# ProProject_AstrOnStep_2024-04-22.net
KiCad netlist of a schematic drawn in EasyEDA Pro
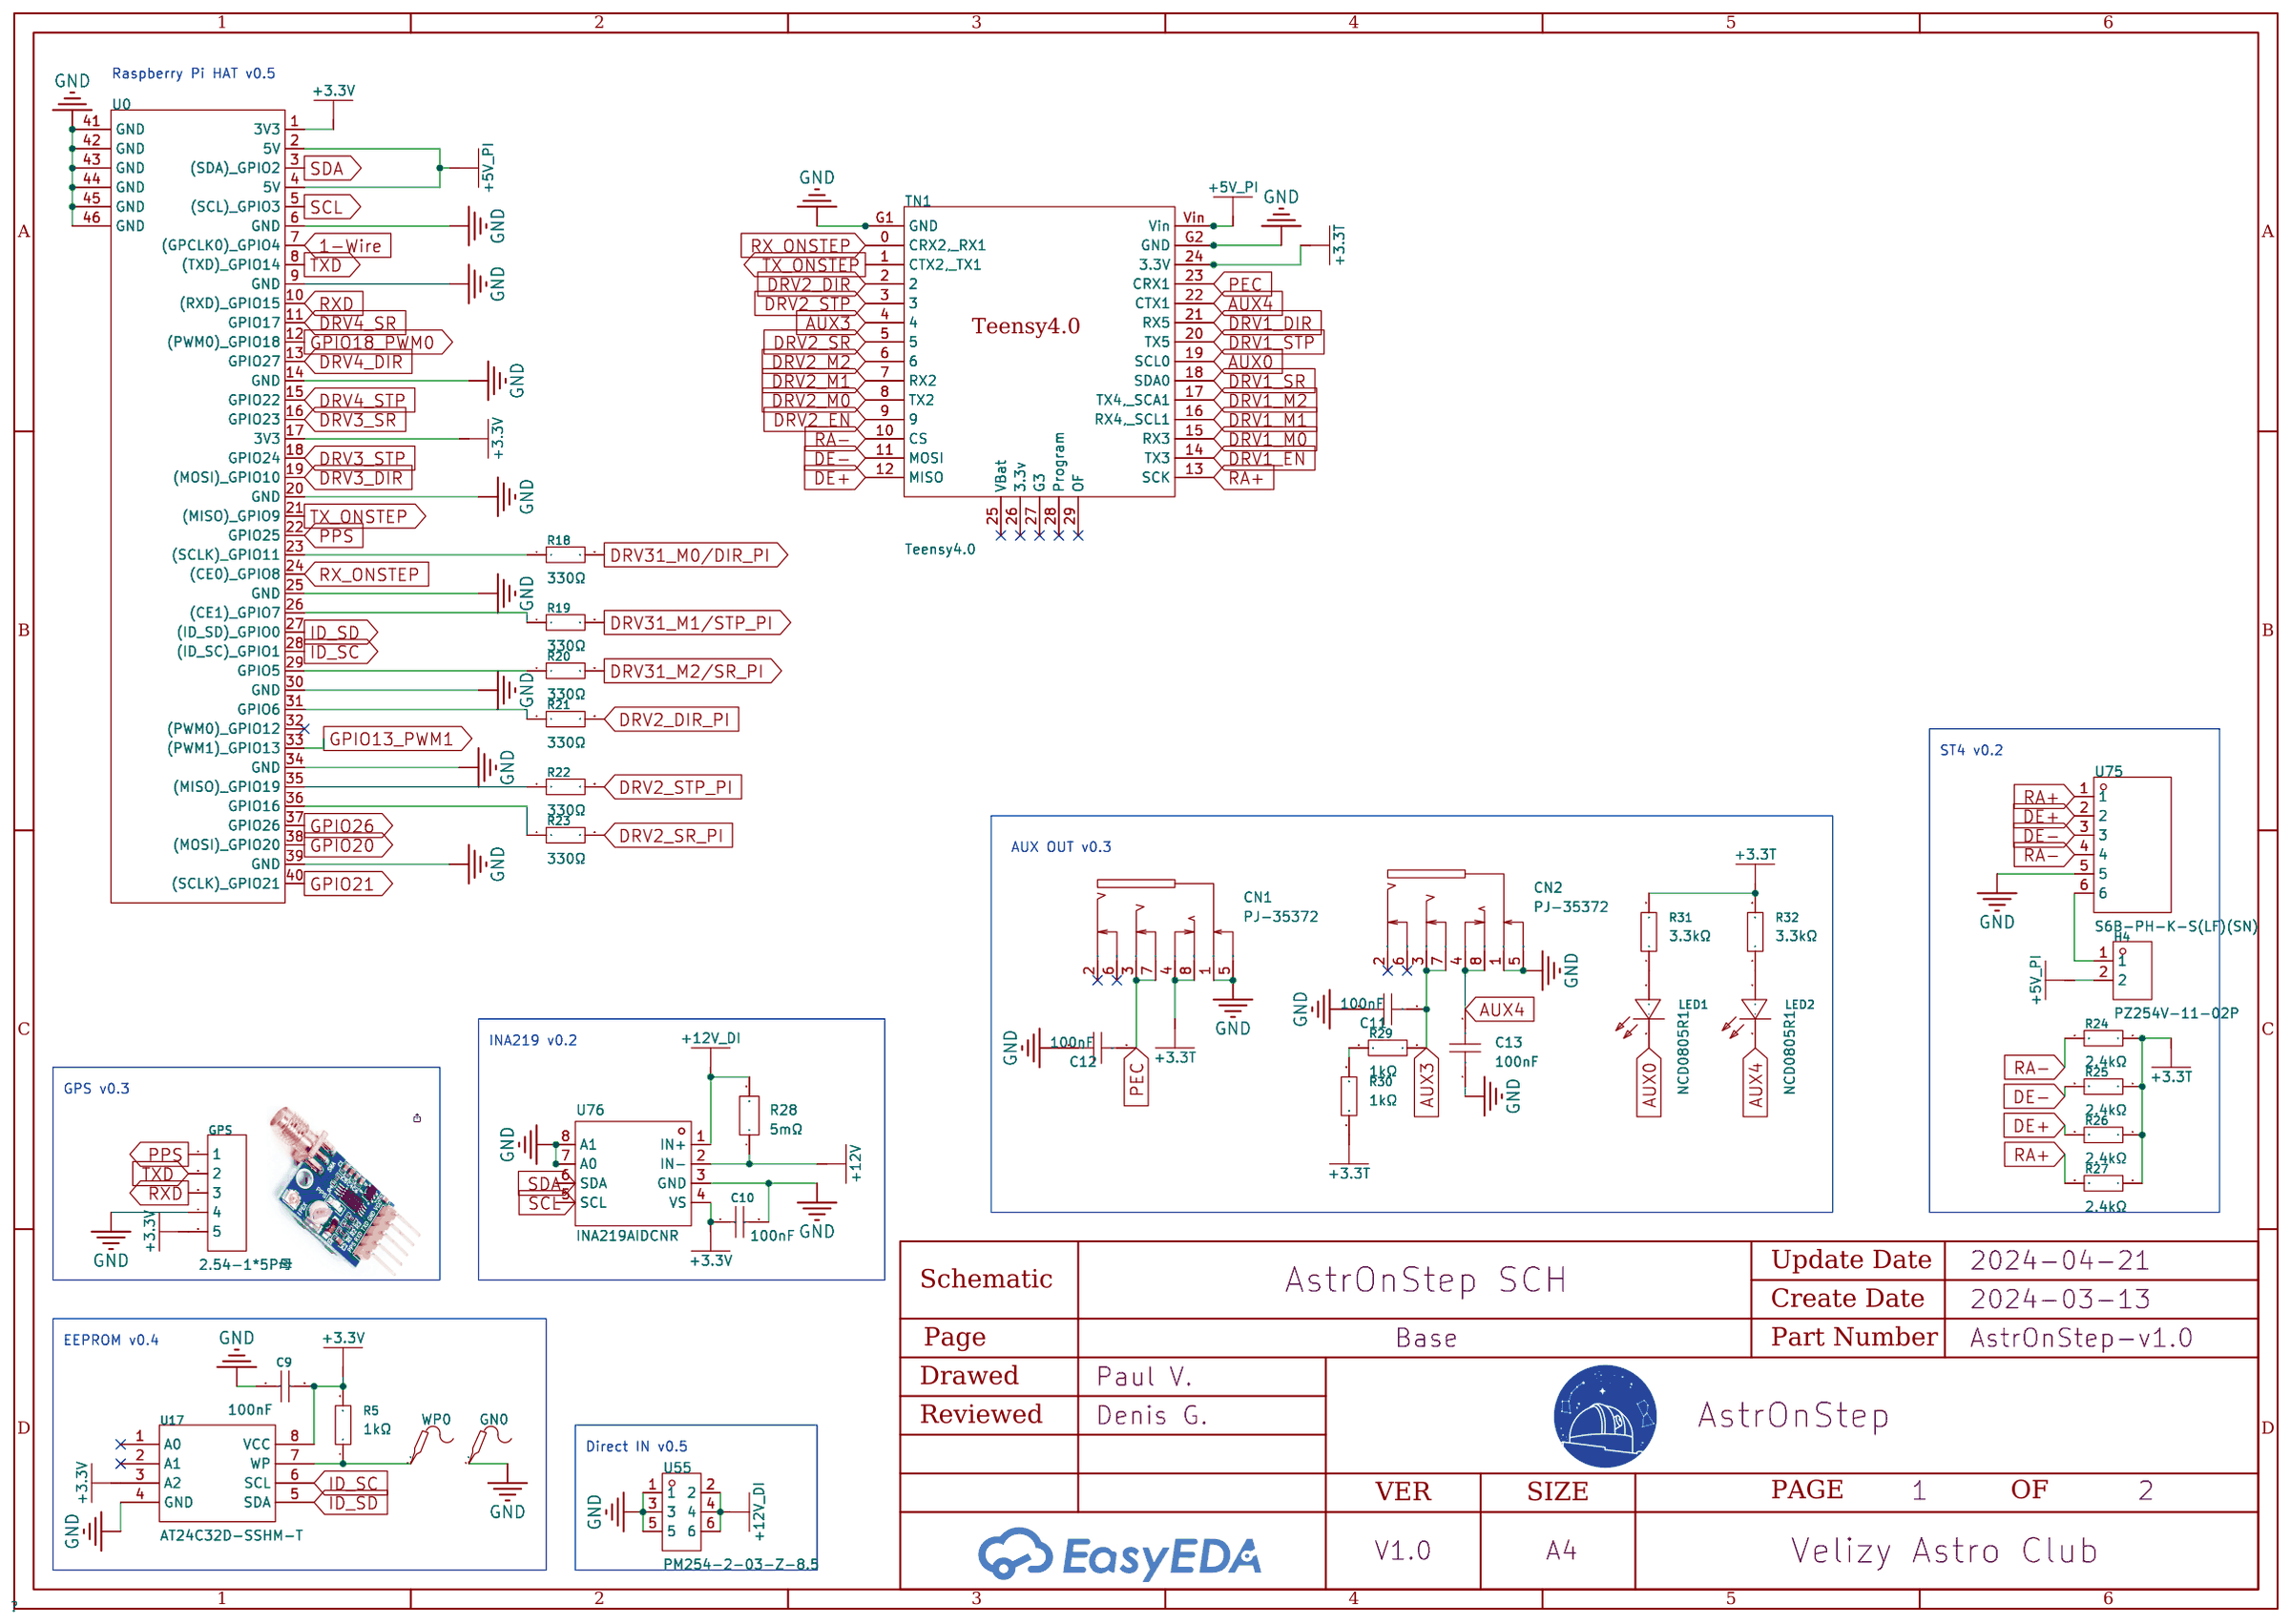
[diagram p0: Base]
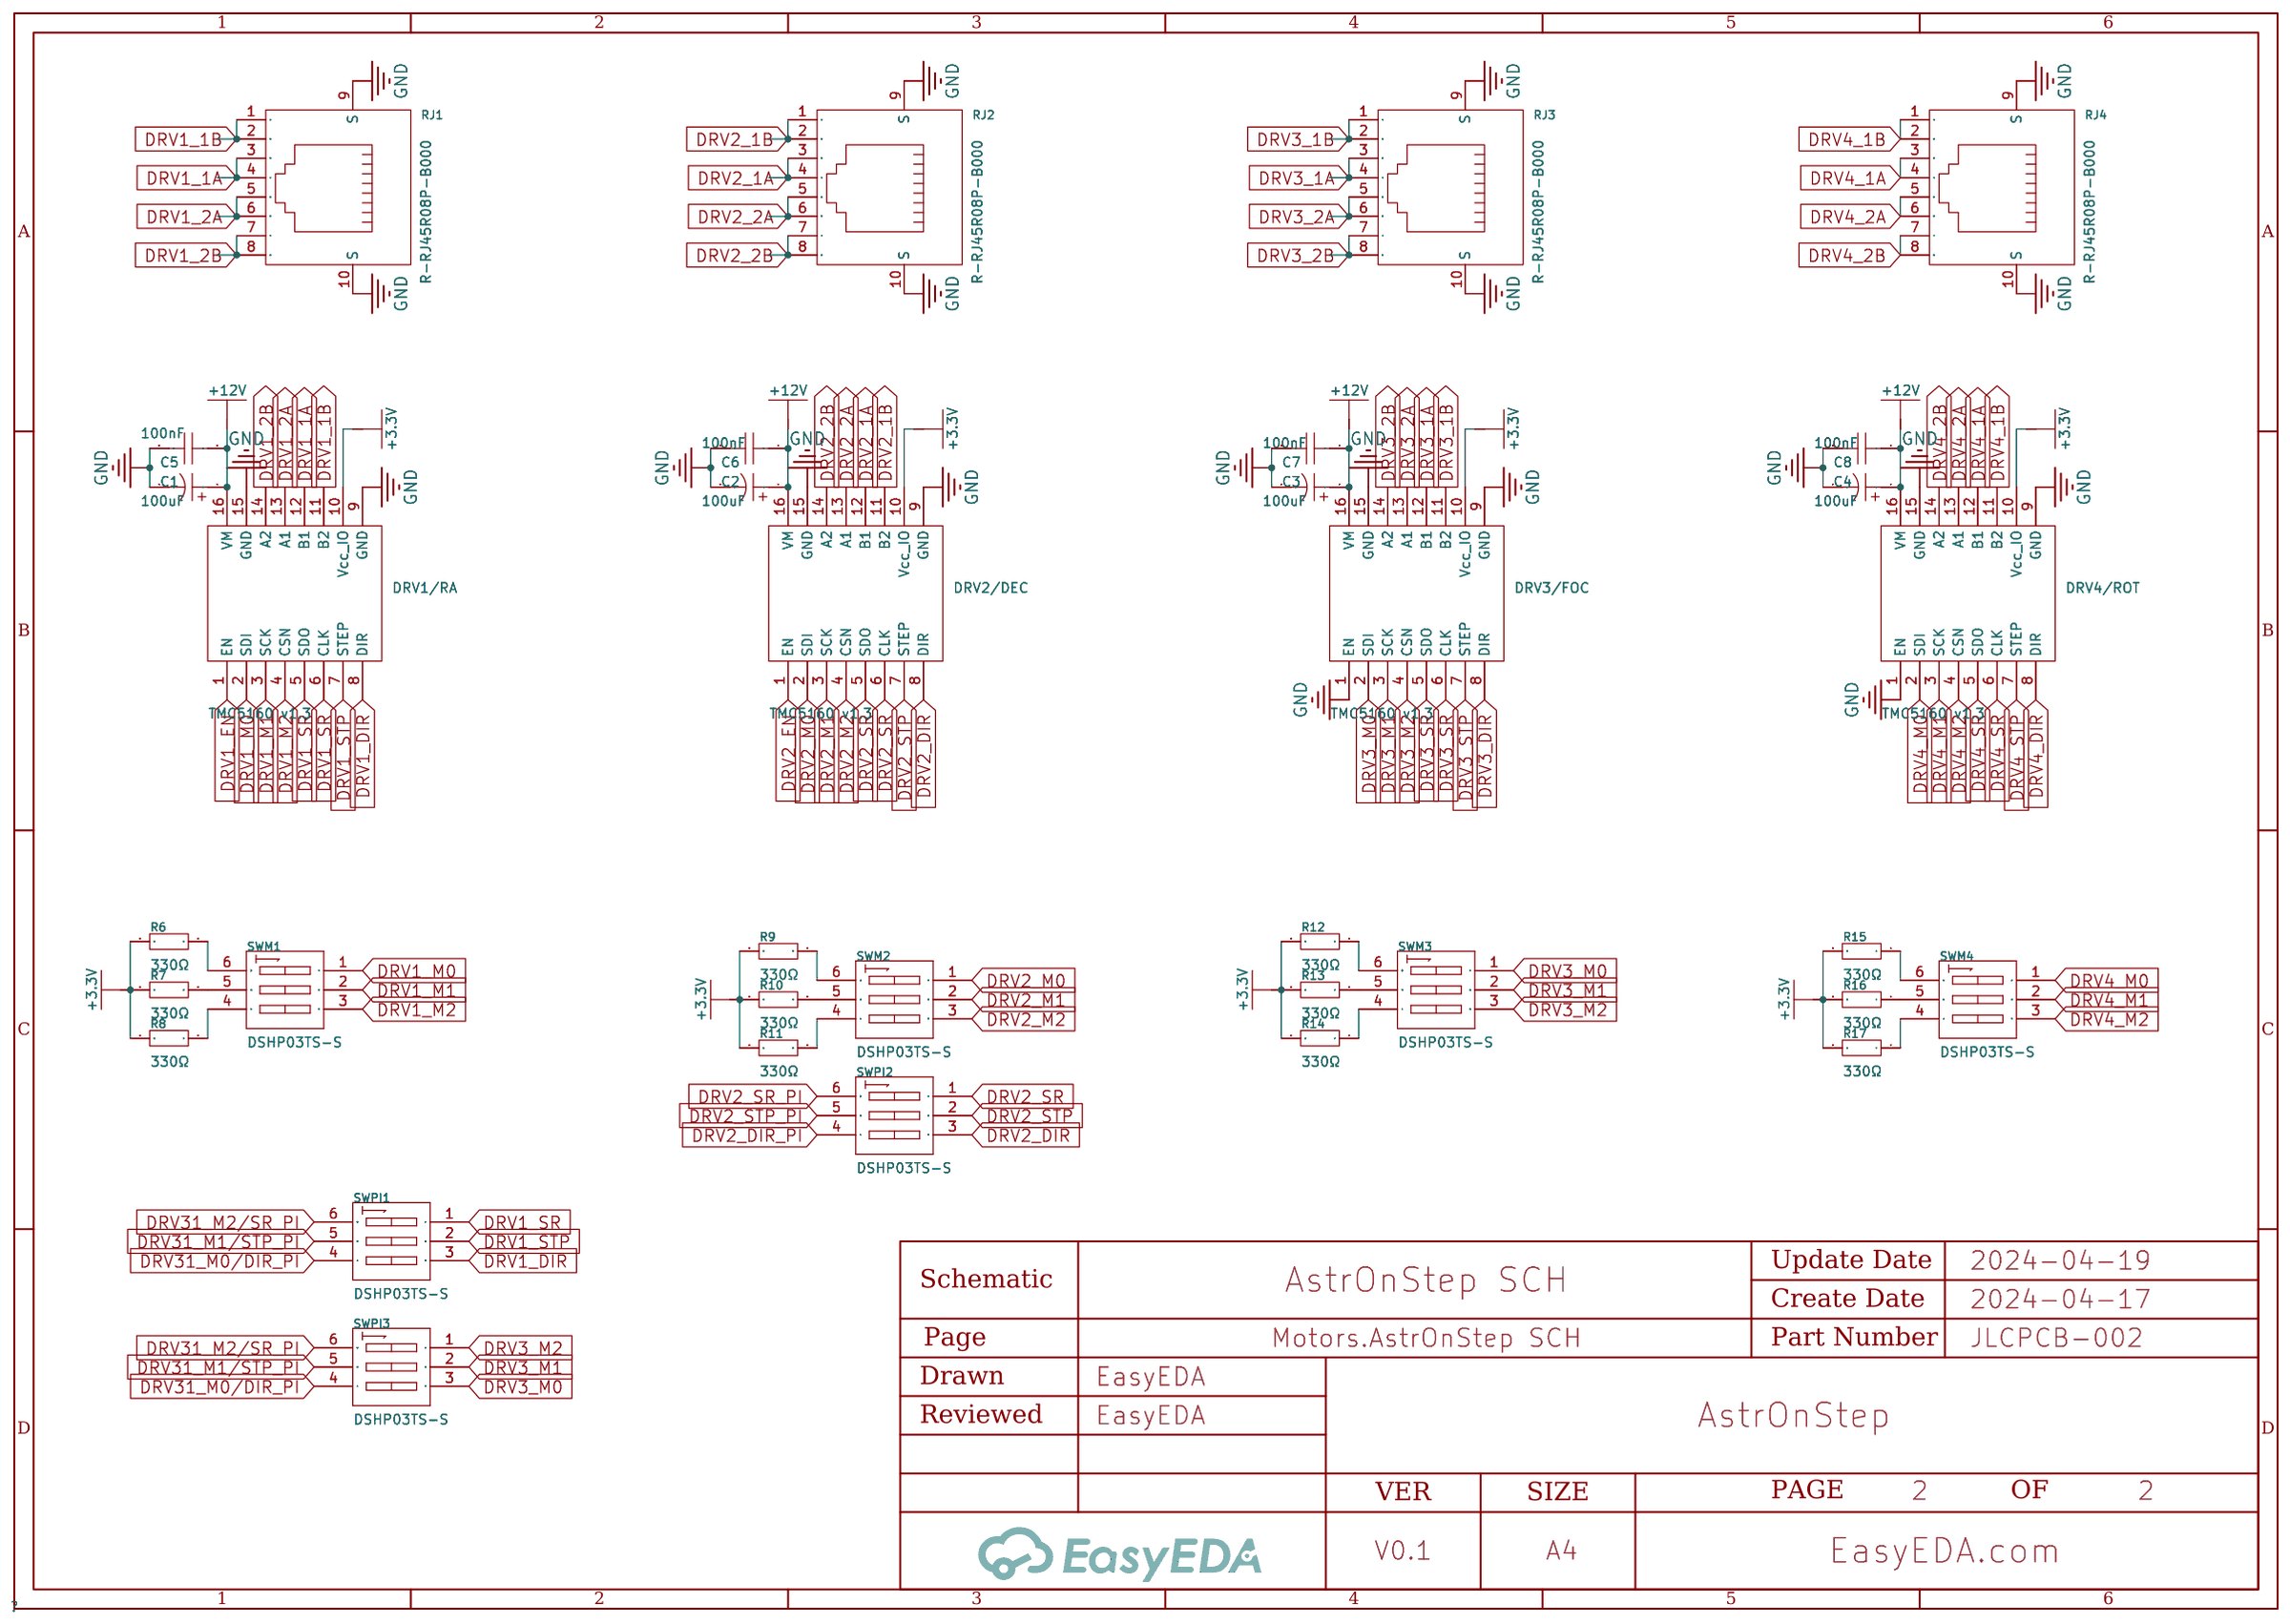
[diagram p1: Motors]

(export (version "E")
  (design (tool "Eeschema 10.0.6"))
  (components
    (comp (ref "C9")
      (value "100nF")
      (footprint "easyedapro:C0402")
      (fields
        (field (name "Manufacturer Part") "CL05B104KO5NNNC")
        (field (name "Manufacturer") "SAMSUNG(三星)")
      )
      (libsource (lib "easyedapro") (part "CL05B104KO5NNNC"))
    )
    (comp (ref "C10")
      (value "100nF")
      (footprint "easyedapro:C0402")
      (fields
        (field (name "Manufacturer Part") "CL05B104KO5NNNC")
        (field (name "Manufacturer") "SAMSUNG(三星)")
      )
      (libsource (lib "easyedapro") (part "CL05B104KO5NNNC"))
    )
    (comp (ref "C11")
      (value "100nF")
      (footprint "easyedapro:C0603")
      (fields
        (field (name "Manufacturer Part") "CC0603KRX7R9BB104")
        (field (name "Manufacturer") "YAGEO(国巨)")
      )
      (libsource (lib "easyedapro") (part "CC0603KRX7R9BB104"))
    )
    (comp (ref "C12")
      (value "100nF")
      (footprint "easyedapro:C0603")
      (fields
        (field (name "Manufacturer Part") "CC0603KRX7R9BB104")
        (field (name "Manufacturer") "YAGEO(国巨)")
      )
      (libsource (lib "easyedapro") (part "CC0603KRX7R9BB104"))
    )
    (comp (ref "C13")
      (value "100nF")
      (footprint "easyedapro:C0603")
      (fields
        (field (name "Manufacturer Part") "CC0603KRX7R9BB104")
        (field (name "Manufacturer") "YAGEO(国巨)")
      )
      (libsource (lib "easyedapro") (part "CC0603KRX7R9BB104"))
    )
    (comp (ref "CN1")
      (value "PJ-35372")
      (footprint "easyedapro:AUDIO-TH_PJ-35372")
      (fields (field (name "Manufacturer") "XKB Connectivity(中国星坤)"))
      (libsource (lib "easyedapro") (part "PJ-35372"))
    )
    (comp (ref "CN2")
      (value "PJ-35372")
      (footprint "easyedapro:AUDIO-TH_PJ-35372")
      (fields (field (name "Manufacturer") "XKB Connectivity(中国星坤)"))
      (libsource (lib "easyedapro") (part "PJ-35372"))
    )
    (comp (ref "GN0")
      (value "~")
      (footprint "easyedapro:Test-Point-0.5mm")
      (description "Test Point 测试点")
      (libsource (lib "easyedapro") (part "Test-Point"))
    )
    (comp (ref "GPS")
      (value "2.54-1*5P母")
      (footprint "easyedapro:HDR-TH_5P-P2.54-V-F")
      (fields (field (name "Manufacturer") "BOOMELE(博穆精密)"))
      (libsource (lib "easyedapro") (part "Header-Female-2.54_1x5"))
    )
    (comp (ref "H4")
      (value "PZ254V-11-02P")
      (footprint "easyedapro:HDR-TH_2P-P2.54-V-M")
      (fields (field (name "Manufacturer") "XFCN(兴飞)"))
      (libsource (lib "easyedapro") (part "PZ254V-11-02P"))
    )
    (comp (ref "LED1")
      (value "NCD0805R1")
      (footprint "easyedapro:LED0805-R-RD")
      (fields (field (name "Manufacturer") "国星光电"))
      (libsource (lib "easyedapro") (part "FC-2012HRK-620D"))
    )
    (comp (ref "LED2")
      (value "NCD0805R1")
      (footprint "easyedapro:LED0805-R-RD")
      (fields (field (name "Manufacturer") "国星光电"))
      (libsource (lib "easyedapro") (part "FC-2012HRK-620D"))
    )
    (comp (ref "R5")
      (value "1kΩ")
      (footprint "easyedapro:R0402")
      (fields
        (field (name "Manufacturer Part") "0402WGF1001TCE")
        (field (name "Manufacturer") "UNI-ROYAL(厚声)")
      )
      (libsource (lib "easyedapro") (part "0402WGF1001TCE"))
    )
    (comp (ref "R18")
      (value "330Ω")
      (footprint "easyedapro:R0402")
      (fields
        (field (name "Manufacturer Part") "0402WGF3300TCE")
        (field (name "Manufacturer") "UNI-ROYAL(厚声)")
      )
      (libsource (lib "easyedapro") (part "0402WGF3300TCE"))
    )
    (comp (ref "R19")
      (value "330Ω")
      (footprint "easyedapro:R0402")
      (fields
        (field (name "Manufacturer Part") "0402WGF3300TCE")
        (field (name "Manufacturer") "UNI-ROYAL(厚声)")
      )
      (libsource (lib "easyedapro") (part "0402WGF3300TCE"))
    )
    (comp (ref "R20")
      (value "330Ω")
      (footprint "easyedapro:R0402")
      (fields
        (field (name "Manufacturer Part") "0402WGF3300TCE")
        (field (name "Manufacturer") "UNI-ROYAL(厚声)")
      )
      (libsource (lib "easyedapro") (part "0402WGF3300TCE"))
    )
    (comp (ref "R21")
      (value "330Ω")
      (footprint "easyedapro:R0402")
      (fields
        (field (name "Manufacturer Part") "0402WGF3300TCE")
        (field (name "Manufacturer") "UNI-ROYAL(厚声)")
      )
      (libsource (lib "easyedapro") (part "0402WGF3300TCE"))
    )
    (comp (ref "R22")
      (value "330Ω")
      (footprint "easyedapro:R0402")
      (fields
        (field (name "Manufacturer Part") "0402WGF3300TCE")
        (field (name "Manufacturer") "UNI-ROYAL(厚声)")
      )
      (libsource (lib "easyedapro") (part "0402WGF3300TCE"))
    )
    (comp (ref "R23")
      (value "330Ω")
      (footprint "easyedapro:R0402")
      (fields
        (field (name "Manufacturer Part") "0402WGF3300TCE")
        (field (name "Manufacturer") "UNI-ROYAL(厚声)")
      )
      (libsource (lib "easyedapro") (part "0402WGF3300TCE"))
    )
    (comp (ref "R24")
      (value "2.4kΩ")
      (footprint "easyedapro:R0603")
      (fields
        (field (name "Manufacturer Part") "0603WAF2401T5E")
        (field (name "Manufacturer") "UNI-ROYAL(厚声)")
      )
      (libsource (lib "easyedapro") (part "0603WAF2401T5E"))
    )
    (comp (ref "R25")
      (value "2.4kΩ")
      (footprint "easyedapro:R0603")
      (fields
        (field (name "Manufacturer Part") "0603WAF2401T5E")
        (field (name "Manufacturer") "UNI-ROYAL(厚声)")
      )
      (libsource (lib "easyedapro") (part "0603WAF2401T5E"))
    )
    (comp (ref "R26")
      (value "2.4kΩ")
      (footprint "easyedapro:R0603")
      (fields
        (field (name "Manufacturer Part") "0603WAF2401T5E")
        (field (name "Manufacturer") "UNI-ROYAL(厚声)")
      )
      (libsource (lib "easyedapro") (part "0603WAF2401T5E"))
    )
    (comp (ref "R27")
      (value "2.4kΩ")
      (footprint "easyedapro:R0603")
      (fields
        (field (name "Manufacturer Part") "0603WAF2401T5E")
        (field (name "Manufacturer") "UNI-ROYAL(厚声)")
      )
      (libsource (lib "easyedapro") (part "0603WAF2401T5E"))
    )
    (comp (ref "R28")
      (value "5mΩ")
      (footprint "easyedapro:R2512")
      (fields
        (field (name "Manufacturer Part") "PA2512FKF7T0R005E")
        (field (name "Manufacturer") "YAGEO(国巨)")
      )
      (libsource (lib "easyedapro") (part "PA2512FKF7T0R005E"))
    )
    (comp (ref "R29")
      (value "1kΩ")
      (footprint "easyedapro:R0402")
      (fields
        (field (name "Manufacturer Part") "0402WGF1001TCE")
        (field (name "Manufacturer") "UNI-ROYAL(厚声)")
      )
      (libsource (lib "easyedapro") (part "0402WGF1001TCE"))
    )
    (comp (ref "R30")
      (value "1kΩ")
      (footprint "easyedapro:R0402")
      (fields
        (field (name "Manufacturer Part") "0402WGF1001TCE")
        (field (name "Manufacturer") "UNI-ROYAL(厚声)")
      )
      (libsource (lib "easyedapro") (part "0402WGF1001TCE"))
    )
    (comp (ref "R31")
      (value "3.3kΩ")
      (footprint "easyedapro:R0402")
      (fields
        (field (name "Manufacturer Part") "0402WGF3301TCE")
        (field (name "Manufacturer") "UNI-ROYAL(厚声)")
      )
      (libsource (lib "easyedapro") (part "0402WGF3301TCE"))
    )
    (comp (ref "R32")
      (value "3.3kΩ")
      (footprint "easyedapro:R0402")
      (fields
        (field (name "Manufacturer Part") "0402WGF3301TCE")
        (field (name "Manufacturer") "UNI-ROYAL(厚声)")
      )
      (libsource (lib "easyedapro") (part "0402WGF3301TCE"))
    )
    (comp (ref "TN1")
      (value "Teensy4.0")
      (footprint "easyedapro:TEENSY4.0")
      (libsource (lib "easyedapro") (part "Teensy4.0"))
    )
    (comp (ref "U0")
      (value "RASPI HAT FULL")
      (fields (field (name "Manufacturer Part") "RaspberryPi 3"))
      (libsource (lib "easyedapro") (part "RASPI HAT FULL - NO OUTLINE"))
    )
    (comp (ref "U17")
      (value "AT24C32D-SSHM-T")
      (footprint "easyedapro:SOIC-8_L5.0-W4.0-P1.27-LS6.0-BL")
      (fields (field (name "Manufacturer") "MICROCHIP(美国微芯)"))
      (libsource (lib "easyedapro") (part "AT24C32D-SSHM-T"))
    )
    (comp (ref "U55")
      (value "PM254-2-03-Z-8.5")
      (footprint "easyedapro:HDR-TH_6P-P2.54-V-F-R2-C3-S2.54")
      (fields (field (name "Manufacturer") "HCTL(华灿天禄)"))
      (libsource (lib "easyedapro") (part "PM254-2-03-Z-8.5"))
    )
    (comp (ref "U75")
      (value "S6B-PH-K-S(LF)(SN)")
      (footprint "easyedapro:CONN-TH_6P-P2.00_S6B-PH-K-S-LF-SN")
      (fields (field (name "Manufacturer") "JST"))
      (libsource (lib "easyedapro") (part "S6B-PH-K-S-(LF)(SN)"))
    )
    (comp (ref "U76")
      (value "INA219AIDCNR")
      (footprint "easyedapro:SOT-23-8_L3.0-W1.7-P0.65-LS2.8-BR")
      (fields (field (name "Manufacturer") "TI(德州仪器)"))
      (libsource (lib "easyedapro") (part "INA219AIDCNR"))
    )
    (comp (ref "WP0")
      (value "~")
      (footprint "easyedapro:Test-Point-0.5mm")
      (description "Test Point 测试点")
      (libsource (lib "easyedapro") (part "Test-Point"))
    )
    (comp (ref "C1")
      (value "100uF")
      (footprint "easyedapro:CAP-SMD_BD6.3-L6.6-W6.6-LS7.3-FD")
      (fields (field (name "Manufacturer Part") "RST100UF25V004") (field (name "Manufacturer") "KNSCHA(科尼盛)"))
      (libsource (lib "easyedapro") (part "RST100UF25V004"))
    )
    (comp (ref "C2")
      (value "100uF")
      (footprint "easyedapro:CAP-SMD_BD6.3-L6.6-W6.6-LS7.3-FD")
      (fields (field (name "Manufacturer Part") "RST100UF25V004") (field (name "Manufacturer") "KNSCHA(科尼盛)"))
      (libsource (lib "easyedapro") (part "RST100UF25V004"))
    )
    (comp (ref "C3")
      (value "100uF")
      (footprint "easyedapro:CAP-SMD_BD6.3-L6.6-W6.6-LS7.3-FD")
      (fields (field (name "Manufacturer Part") "RST100UF25V004") (field (name "Manufacturer") "KNSCHA(科尼盛)"))
      (libsource (lib "easyedapro") (part "RST100UF25V004"))
    )
    (comp (ref "C4")
      (value "100uF")
      (footprint "easyedapro:CAP-SMD_BD6.3-L6.6-W6.6-LS7.3-FD")
      (fields (field (name "Manufacturer Part") "RST100UF25V004") (field (name "Manufacturer") "KNSCHA(科尼盛)"))
      (libsource (lib "easyedapro") (part "RST100UF25V004"))
    )
    (comp (ref "C5")
      (value "100nF")
      (footprint "easyedapro:C0603")
      (fields
        (field (name "Manufacturer Part") "CC0603KRX7R9BB104")
        (field (name "Manufacturer") "YAGEO(国巨)")
      )
      (libsource (lib "easyedapro") (part "CC0603KRX7R9BB104"))
    )
    (comp (ref "C6")
      (value "100nF")
      (footprint "easyedapro:C0603")
      (fields
        (field (name "Manufacturer Part") "CC0603KRX7R9BB104")
        (field (name "Manufacturer") "YAGEO(国巨)")
      )
      (libsource (lib "easyedapro") (part "CC0603KRX7R9BB104"))
    )
    (comp (ref "C7")
      (value "100nF")
      (footprint "easyedapro:C0603")
      (fields
        (field (name "Manufacturer Part") "CC0603KRX7R9BB104")
        (field (name "Manufacturer") "YAGEO(国巨)")
      )
      (libsource (lib "easyedapro") (part "CC0603KRX7R9BB104"))
    )
    (comp (ref "C8")
      (value "100nF")
      (footprint "easyedapro:C0603")
      (fields
        (field (name "Manufacturer Part") "CC0603KRX7R9BB104")
        (field (name "Manufacturer") "YAGEO(国巨)")
      )
      (libsource (lib "easyedapro") (part "CC0603KRX7R9BB104"))
    )
    (comp (ref "DRV1/RA")
      (value "TMC5160 v1.3")
      (footprint "easyedapro:TMC5160")
      (fields (field (name "Manufacturer") "Bigtreetech"))
      (libsource (lib "easyedapro") (part "TMC5160 v1.3"))
    )
    (comp (ref "DRV2/DEC")
      (value "TMC5160 v1.3")
      (footprint "easyedapro:TMC5160")
      (fields (field (name "Manufacturer") "Bigtreetech"))
      (libsource (lib "easyedapro") (part "TMC5160 v1.3"))
    )
    (comp (ref "DRV3/FOC")
      (value "TMC5160 v1.3")
      (footprint "easyedapro:TMC5160")
      (fields (field (name "Manufacturer") "Bigtreetech"))
      (libsource (lib "easyedapro") (part "TMC5160 v1.3"))
    )
    (comp (ref "DRV4/ROT")
      (value "TMC5160 v1.3")
      (footprint "easyedapro:TMC5160")
      (fields (field (name "Manufacturer") "Bigtreetech"))
      (libsource (lib "easyedapro") (part "TMC5160 v1.3"))
    )
    (comp (ref "R6")
      (value "330Ω")
      (footprint "easyedapro:R0402")
      (fields
        (field (name "Manufacturer Part") "0402WGF3300TCE")
        (field (name "Manufacturer") "UNI-ROYAL(厚声)")
      )
      (libsource (lib "easyedapro") (part "0402WGF3300TCE"))
    )
    (comp (ref "R7")
      (value "330Ω")
      (footprint "easyedapro:R0402")
      (fields
        (field (name "Manufacturer Part") "0402WGF3300TCE")
        (field (name "Manufacturer") "UNI-ROYAL(厚声)")
      )
      (libsource (lib "easyedapro") (part "0402WGF3300TCE"))
    )
    (comp (ref "R8")
      (value "330Ω")
      (footprint "easyedapro:R0402")
      (fields
        (field (name "Manufacturer Part") "0402WGF3300TCE")
        (field (name "Manufacturer") "UNI-ROYAL(厚声)")
      )
      (libsource (lib "easyedapro") (part "0402WGF3300TCE"))
    )
    (comp (ref "R9")
      (value "330Ω")
      (footprint "easyedapro:R0402")
      (fields
        (field (name "Manufacturer Part") "0402WGF3300TCE")
        (field (name "Manufacturer") "UNI-ROYAL(厚声)")
      )
      (libsource (lib "easyedapro") (part "0402WGF3300TCE"))
    )
    (comp (ref "R10")
      (value "330Ω")
      (footprint "easyedapro:R0402")
      (fields
        (field (name "Manufacturer Part") "0402WGF3300TCE")
        (field (name "Manufacturer") "UNI-ROYAL(厚声)")
      )
      (libsource (lib "easyedapro") (part "0402WGF3300TCE"))
    )
    (comp (ref "R11")
      (value "330Ω")
      (footprint "easyedapro:R0402")
      (fields
        (field (name "Manufacturer Part") "0402WGF3300TCE")
        (field (name "Manufacturer") "UNI-ROYAL(厚声)")
      )
      (libsource (lib "easyedapro") (part "0402WGF3300TCE"))
    )
    (comp (ref "R12")
      (value "330Ω")
      (footprint "easyedapro:R0402")
      (fields
        (field (name "Manufacturer Part") "0402WGF3300TCE")
        (field (name "Manufacturer") "UNI-ROYAL(厚声)")
      )
      (libsource (lib "easyedapro") (part "0402WGF3300TCE"))
    )
    (comp (ref "R13")
      (value "330Ω")
      (footprint "easyedapro:R0402")
      (fields
        (field (name "Manufacturer Part") "0402WGF3300TCE")
        (field (name "Manufacturer") "UNI-ROYAL(厚声)")
      )
      (libsource (lib "easyedapro") (part "0402WGF3300TCE"))
    )
    (comp (ref "R14")
      (value "330Ω")
      (footprint "easyedapro:R0402")
      (fields
        (field (name "Manufacturer Part") "0402WGF3300TCE")
        (field (name "Manufacturer") "UNI-ROYAL(厚声)")
      )
      (libsource (lib "easyedapro") (part "0402WGF3300TCE"))
    )
    (comp (ref "R15")
      (value "330Ω")
      (footprint "easyedapro:R0402")
      (fields
        (field (name "Manufacturer Part") "0402WGF3300TCE")
        (field (name "Manufacturer") "UNI-ROYAL(厚声)")
      )
      (libsource (lib "easyedapro") (part "0402WGF3300TCE"))
    )
    (comp (ref "R16")
      (value "330Ω")
      (footprint "easyedapro:R0402")
      (fields
        (field (name "Manufacturer Part") "0402WGF3300TCE")
        (field (name "Manufacturer") "UNI-ROYAL(厚声)")
      )
      (libsource (lib "easyedapro") (part "0402WGF3300TCE"))
    )
    (comp (ref "R17")
      (value "330Ω")
      (footprint "easyedapro:R0402")
      (fields
        (field (name "Manufacturer Part") "0402WGF3300TCE")
        (field (name "Manufacturer") "UNI-ROYAL(厚声)")
      )
      (libsource (lib "easyedapro") (part "0402WGF3300TCE"))
    )
    (comp (ref "RJ1")
      (value "R-RJ45R08P-B000")
      (footprint "easyedapro:RJ45-TH_R-RJ45R08P-B000")
      (fields (field (name "Manufacturer") "Ckmtw(灿科盟)"))
      (libsource (lib "easyedapro") (part "R-RJ45R08P-B000"))
    )
    (comp (ref "RJ2")
      (value "R-RJ45R08P-B000")
      (footprint "easyedapro:RJ45-TH_R-RJ45R08P-B000")
      (fields (field (name "Manufacturer") "Ckmtw(灿科盟)"))
      (libsource (lib "easyedapro") (part "R-RJ45R08P-B000"))
    )
    (comp (ref "RJ3")
      (value "R-RJ45R08P-B000")
      (footprint "easyedapro:RJ45-TH_R-RJ45R08P-B000")
      (fields (field (name "Manufacturer") "Ckmtw(灿科盟)"))
      (libsource (lib "easyedapro") (part "R-RJ45R08P-B000"))
    )
    (comp (ref "RJ4")
      (value "R-RJ45R08P-B000")
      (footprint "easyedapro:RJ45-TH_R-RJ45R08P-B000")
      (fields (field (name "Manufacturer") "Ckmtw(灿科盟)"))
      (libsource (lib "easyedapro") (part "R-RJ45R08P-B000"))
    )
    (comp (ref "SWM1")
      (value "DSHP03TS-S")
      (footprint "easyedapro:SW-SMD_DSHP03TS-S")
      (fields (field (name "Manufacturer") "XKB Connectivity(中国星坤)"))
      (libsource (lib "easyedapro") (part "DSHP03TS-S"))
    )
    (comp (ref "SWM2")
      (value "DSHP03TS-S")
      (footprint "easyedapro:SW-SMD_DSHP03TS-S")
      (fields (field (name "Manufacturer") "XKB Connectivity(中国星坤)"))
      (libsource (lib "easyedapro") (part "DSHP03TS-S"))
    )
    (comp (ref "SWM3")
      (value "DSHP03TS-S")
      (footprint "easyedapro:SW-SMD_DSHP03TS-S")
      (fields (field (name "Manufacturer") "XKB Connectivity(中国星坤)"))
      (libsource (lib "easyedapro") (part "DSHP03TS-S"))
    )
    (comp (ref "SWM4")
      (value "DSHP03TS-S")
      (footprint "easyedapro:SW-SMD_DSHP03TS-S")
      (fields (field (name "Manufacturer") "XKB Connectivity(中国星坤)"))
      (libsource (lib "easyedapro") (part "DSHP03TS-S"))
    )
    (comp (ref "SWPI1")
      (value "DSHP03TS-S")
      (footprint "easyedapro:SW-SMD_DSHP03TS-S")
      (fields (field (name "Manufacturer") "XKB Connectivity(中国星坤)"))
      (libsource (lib "easyedapro") (part "DSHP03TS-S"))
    )
    (comp (ref "SWPI2")
      (value "DSHP03TS-S")
      (footprint "easyedapro:SW-SMD_DSHP03TS-S")
      (fields (field (name "Manufacturer") "XKB Connectivity(中国星坤)"))
      (libsource (lib "easyedapro") (part "DSHP03TS-S"))
    )
    (comp (ref "SWPI3")
      (value "DSHP03TS-S")
      (footprint "easyedapro:SW-SMD_DSHP03TS-S")
      (fields (field (name "Manufacturer") "XKB Connectivity(中国星坤)"))
      (libsource (lib "easyedapro") (part "DSHP03TS-S"))
    )
  )
  (nets
    (net (code "1") (name "+3.3T") (class "Default")
      (node (ref "CN1") (pin "4") (pinfunction "4_4") (pintype "input"))
      (node (ref "CN1") (pin "8") (pinfunction "8_8") (pintype "input"))
      (node (ref "R24") (pin "1") (pinfunction "1_1") (pintype "input"))
      (node (ref "R25") (pin "1") (pinfunction "1_1") (pintype "input"))
      (node (ref "R26") (pin "1") (pinfunction "1_1") (pintype "input"))
      (node (ref "R27") (pin "1") (pinfunction "1_1") (pintype "input"))
      (node (ref "R30") (pin "1") (pinfunction "1_1") (pintype "input"))
      (node (ref "R31") (pin "2") (pinfunction "2_2") (pintype "input"))
      (node (ref "R32") (pin "2") (pinfunction "2_2") (pintype "input"))
      (node (ref "TN1") (pin "24") (pinfunction "3.3V_24") (pintype "input"))
    )
    (net (code "2") (name "+3.3V") (class "Default")
      (node (ref "C10") (pin "1") (pinfunction "1_1") (pintype "input"))
      (node (ref "C9") (pin "2") (pinfunction "2_2") (pintype "input"))
      (node (ref "DRV1/RA") (pin "10") (pinfunction "Vcc_IO_10") (pintype "unspecified"))
      (node (ref "DRV2/DEC") (pin "10") (pinfunction "Vcc_IO_10") (pintype "unspecified"))
      (node (ref "DRV3/FOC") (pin "10") (pinfunction "Vcc_IO_10") (pintype "unspecified"))
      (node (ref "DRV4/ROT") (pin "10") (pinfunction "Vcc_IO_10") (pintype "unspecified"))
      (node (ref "GPS") (pin "5") (pinfunction "5_5") (pintype "input"))
      (node (ref "R10") (pin "2") (pinfunction "2_2") (pintype "input"))
      (node (ref "R11") (pin "2") (pinfunction "2_2") (pintype "input"))
      (node (ref "R12") (pin "2") (pinfunction "2_2") (pintype "input"))
      (node (ref "R13") (pin "2") (pinfunction "2_2") (pintype "input"))
      (node (ref "R14") (pin "2") (pinfunction "2_2") (pintype "input"))
      (node (ref "R15") (pin "2") (pinfunction "2_2") (pintype "input"))
      (node (ref "R16") (pin "2") (pinfunction "2_2") (pintype "input"))
      (node (ref "R17") (pin "2") (pinfunction "2_2") (pintype "input"))
      (node (ref "R5") (pin "2") (pinfunction "2_2") (pintype "input"))
      (node (ref "R6") (pin "2") (pinfunction "2_2") (pintype "input"))
      (node (ref "R7") (pin "2") (pinfunction "2_2") (pintype "input"))
      (node (ref "R8") (pin "2") (pinfunction "2_2") (pintype "input"))
      (node (ref "R9") (pin "2") (pinfunction "2_2") (pintype "input"))
      (node (ref "U0") (pin "1") (pinfunction "3V3_1") (pintype "unspecified"))
      (node (ref "U0") (pin "17") (pinfunction "3V3_17") (pintype "unspecified"))
      (node (ref "U17") (pin "3") (pinfunction "A2_3") (pintype "input"))
      (node (ref "U17") (pin "8") (pinfunction "VCC_8") (pintype "input"))
      (node (ref "U76") (pin "4") (pinfunction "VS_4") (pintype "unspecified"))
    )
    (net (code "3") (name "+5V_PI") (class "Default")
      (node (ref "H4") (pin "2") (pinfunction "2_2") (pintype "input"))
      (node (ref "TN1") (pin "Vin") (pinfunction "Vin_Vin") (pintype "input"))
      (node (ref "U0") (pin "2") (pinfunction "5V_2") (pintype "unspecified"))
      (node (ref "U0") (pin "4") (pinfunction "5V_4") (pintype "unspecified"))
    )
    (net (code "4") (name "+12V") (class "Default")
      (node (ref "C1") (pin "1") (pinfunction "1_1") (pintype "input"))
      (node (ref "C2") (pin "1") (pinfunction "1_1") (pintype "input"))
      (node (ref "C3") (pin "1") (pinfunction "1_1") (pintype "input"))
      (node (ref "C4") (pin "1") (pinfunction "1_1") (pintype "input"))
      (node (ref "C5") (pin "1") (pinfunction "1_1") (pintype "input"))
      (node (ref "C6") (pin "1") (pinfunction "1_1") (pintype "input"))
      (node (ref "C7") (pin "1") (pinfunction "1_1") (pintype "input"))
      (node (ref "C8") (pin "1") (pinfunction "1_1") (pintype "input"))
      (node (ref "DRV1/RA") (pin "16") (pinfunction "VM_16") (pintype "unspecified"))
      (node (ref "DRV2/DEC") (pin "16") (pinfunction "VM_16") (pintype "unspecified"))
      (node (ref "DRV3/FOC") (pin "16") (pinfunction "VM_16") (pintype "unspecified"))
      (node (ref "DRV4/ROT") (pin "16") (pinfunction "VM_16") (pintype "unspecified"))
      (node (ref "R28") (pin "1") (pinfunction "1_1") (pintype "unspecified"))
      (node (ref "U76") (pin "2") (pinfunction "IN-_2") (pintype "unspecified"))
    )
    (net (code "5") (name "+12V_DI") (class "Default")
      (node (ref "R28") (pin "2") (pinfunction "2_2") (pintype "unspecified"))
      (node (ref "U55") (pin "2") (pinfunction "2_2") (pintype "unspecified"))
      (node (ref "U55") (pin "4") (pinfunction "4_4") (pintype "unspecified"))
      (node (ref "U55") (pin "6") (pinfunction "6_6") (pintype "unspecified"))
      (node (ref "U76") (pin "1") (pinfunction "IN+_1") (pintype "unspecified"))
    )
    (net (code "6") (name "1-Wire") (class "Default")
      (node (ref "U0") (pin "7") (pinfunction "(GPCLK0)_GPIO4_7") (pintype "unspecified"))
    )
    (net (code "7") (name "AUX0") (class "Default")
      (node (ref "LED1") (pin "2") (pinfunction "-_2") (pintype "input"))
      (node (ref "TN1") (pin "19") (pinfunction "SCL0_19") (pintype "input"))
    )
    (net (code "8") (name "AUX3") (class "Default")
      (node (ref "C11") (pin "1") (pinfunction "1_1") (pintype "input"))
      (node (ref "CN2") (pin "3") (pinfunction "3_3") (pintype "input"))
      (node (ref "CN2") (pin "7") (pinfunction "7_7") (pintype "input"))
      (node (ref "R29") (pin "1") (pinfunction "1_1") (pintype "input"))
      (node (ref "TN1") (pin "4") (pinfunction "4_4") (pintype "input"))
    )
    (net (code "9") (name "AUX4") (class "Default")
      (node (ref "C13") (pin "2") (pinfunction "2_2") (pintype "input"))
      (node (ref "CN2") (pin "4") (pinfunction "4_4") (pintype "input"))
      (node (ref "CN2") (pin "8") (pinfunction "8_8") (pintype "input"))
      (node (ref "LED2") (pin "2") (pinfunction "-_2") (pintype "input"))
      (node (ref "TN1") (pin "22") (pinfunction "CTX1_22") (pintype "input"))
    )
    (net (code "10") (name "DE+") (class "Default")
      (node (ref "R26") (pin "2") (pinfunction "2_2") (pintype "input"))
      (node (ref "TN1") (pin "12") (pinfunction "MISO_12") (pintype "input"))
      (node (ref "U75") (pin "2") (pinfunction "2_2") (pintype "unspecified"))
    )
    (net (code "11") (name "DE-") (class "Default")
      (node (ref "R25") (pin "2") (pinfunction "2_2") (pintype "input"))
      (node (ref "TN1") (pin "11") (pinfunction "MOSI_11") (pintype "input"))
      (node (ref "U75") (pin "3") (pinfunction "3_3") (pintype "unspecified"))
    )
    (net (code "12") (name "DRV1_1A") (class "Default")
      (node (ref "DRV1/RA") (pin "12") (pinfunction "B1_12") (pintype "unspecified"))
      (node (ref "RJ1") (pin "3") (pinfunction "3_3") (pintype "input"))
      (node (ref "RJ1") (pin "4") (pinfunction "4_4") (pintype "input"))
    )
    (net (code "13") (name "DRV1_1B") (class "Default")
      (node (ref "DRV1/RA") (pin "11") (pinfunction "B2_11") (pintype "unspecified"))
      (node (ref "RJ1") (pin "1") (pinfunction "1_1") (pintype "input"))
      (node (ref "RJ1") (pin "2") (pinfunction "2_2") (pintype "input"))
    )
    (net (code "14") (name "DRV1_2A") (class "Default")
      (node (ref "DRV1/RA") (pin "13") (pinfunction "A1_13") (pintype "unspecified"))
      (node (ref "RJ1") (pin "5") (pinfunction "5_5") (pintype "input"))
      (node (ref "RJ1") (pin "6") (pinfunction "6_6") (pintype "input"))
    )
    (net (code "15") (name "DRV1_2B") (class "Default")
      (node (ref "DRV1/RA") (pin "14") (pinfunction "A2_14") (pintype "unspecified"))
      (node (ref "RJ1") (pin "7") (pinfunction "7_7") (pintype "input"))
      (node (ref "RJ1") (pin "8") (pinfunction "8_8") (pintype "input"))
    )
    (net (code "16") (name "DRV1_DIR") (class "Default")
      (node (ref "DRV1/RA") (pin "8") (pinfunction "DIR_8") (pintype "unspecified"))
      (node (ref "SWPI1") (pin "3") (pinfunction "3_3") (pintype "input"))
      (node (ref "TN1") (pin "21") (pinfunction "RX5_21") (pintype "input"))
    )
    (net (code "17") (name "DRV1_EN") (class "Default")
      (node (ref "DRV1/RA") (pin "1") (pinfunction "EN_1") (pintype "unspecified"))
      (node (ref "TN1") (pin "14") (pinfunction "TX3_14") (pintype "input"))
    )
    (net (code "18") (name "DRV1_M0") (class "Default")
      (node (ref "DRV1/RA") (pin "2") (pinfunction "SDI_2") (pintype "unspecified"))
      (node (ref "SWM1") (pin "1") (pinfunction "1_1") (pintype "input"))
      (node (ref "TN1") (pin "15") (pinfunction "RX3_15") (pintype "input"))
    )
    (net (code "19") (name "DRV1_M1") (class "Default")
      (node (ref "DRV1/RA") (pin "3") (pinfunction "SCK_3") (pintype "unspecified"))
      (node (ref "SWM1") (pin "2") (pinfunction "2_2") (pintype "input"))
      (node (ref "TN1") (pin "16") (pinfunction "RX4,_SCL1_16") (pintype "input"))
    )
    (net (code "20") (name "DRV1_M2") (class "Default")
      (node (ref "DRV1/RA") (pin "4") (pinfunction "CSN_4") (pintype "unspecified"))
      (node (ref "SWM1") (pin "3") (pinfunction "3_3") (pintype "input"))
      (node (ref "TN1") (pin "17") (pinfunction "TX4,_SCA1_17") (pintype "input"))
    )
    (net (code "21") (name "DRV1_SR") (class "Default")
      (node (ref "DRV1/RA") (pin "5") (pinfunction "SDO_5") (pintype "unspecified"))
      (node (ref "DRV1/RA") (pin "6") (pinfunction "CLK_6") (pintype "unspecified"))
      (node (ref "SWPI1") (pin "1") (pinfunction "1_1") (pintype "input"))
      (node (ref "TN1") (pin "18") (pinfunction "SDA0_18") (pintype "input"))
    )
    (net (code "22") (name "DRV1_STP") (class "Default")
      (node (ref "DRV1/RA") (pin "7") (pinfunction "STEP_7") (pintype "unspecified"))
      (node (ref "SWPI1") (pin "2") (pinfunction "2_2") (pintype "input"))
      (node (ref "TN1") (pin "20") (pinfunction "TX5_20") (pintype "input"))
    )
    (net (code "23") (name "DRV2_1A") (class "Default")
      (node (ref "DRV2/DEC") (pin "12") (pinfunction "B1_12") (pintype "unspecified"))
      (node (ref "RJ2") (pin "3") (pinfunction "3_3") (pintype "input"))
      (node (ref "RJ2") (pin "4") (pinfunction "4_4") (pintype "input"))
    )
    (net (code "24") (name "DRV2_1B") (class "Default")
      (node (ref "DRV2/DEC") (pin "11") (pinfunction "B2_11") (pintype "unspecified"))
      (node (ref "RJ2") (pin "1") (pinfunction "1_1") (pintype "input"))
      (node (ref "RJ2") (pin "2") (pinfunction "2_2") (pintype "input"))
    )
    (net (code "25") (name "DRV2_2A") (class "Default")
      (node (ref "DRV2/DEC") (pin "13") (pinfunction "A1_13") (pintype "unspecified"))
      (node (ref "RJ2") (pin "5") (pinfunction "5_5") (pintype "input"))
      (node (ref "RJ2") (pin "6") (pinfunction "6_6") (pintype "input"))
    )
    (net (code "26") (name "DRV2_2B") (class "Default")
      (node (ref "DRV2/DEC") (pin "14") (pinfunction "A2_14") (pintype "unspecified"))
      (node (ref "RJ2") (pin "7") (pinfunction "7_7") (pintype "input"))
      (node (ref "RJ2") (pin "8") (pinfunction "8_8") (pintype "input"))
    )
    (net (code "27") (name "DRV2_DIR") (class "Default")
      (node (ref "DRV2/DEC") (pin "8") (pinfunction "DIR_8") (pintype "unspecified"))
      (node (ref "SWPI2") (pin "3") (pinfunction "3_3") (pintype "input"))
      (node (ref "TN1") (pin "2") (pinfunction "2_2") (pintype "input"))
    )
    (net (code "28") (name "DRV2_DIR_PI") (class "Default")
      (node (ref "R21") (pin "2") (pinfunction "2_2") (pintype "input"))
      (node (ref "SWPI2") (pin "4") (pinfunction "4_4") (pintype "input"))
    )
    (net (code "29") (name "DRV2_EN") (class "Default")
      (node (ref "DRV2/DEC") (pin "1") (pinfunction "EN_1") (pintype "unspecified"))
      (node (ref "TN1") (pin "9") (pinfunction "9_9") (pintype "input"))
    )
    (net (code "30") (name "DRV2_M0") (class "Default")
      (node (ref "DRV2/DEC") (pin "2") (pinfunction "SDI_2") (pintype "unspecified"))
      (node (ref "SWM2") (pin "1") (pinfunction "1_1") (pintype "input"))
      (node (ref "TN1") (pin "8") (pinfunction "TX2_8") (pintype "input"))
    )
    (net (code "31") (name "DRV2_M1") (class "Default")
      (node (ref "DRV2/DEC") (pin "3") (pinfunction "SCK_3") (pintype "unspecified"))
      (node (ref "SWM2") (pin "2") (pinfunction "2_2") (pintype "input"))
      (node (ref "TN1") (pin "7") (pinfunction "RX2_7") (pintype "input"))
    )
    (net (code "32") (name "DRV2_M2") (class "Default")
      (node (ref "DRV2/DEC") (pin "4") (pinfunction "CSN_4") (pintype "unspecified"))
      (node (ref "SWM2") (pin "3") (pinfunction "3_3") (pintype "input"))
      (node (ref "TN1") (pin "6") (pinfunction "6_6") (pintype "input"))
    )
    (net (code "33") (name "DRV2_SR") (class "Default")
      (node (ref "DRV2/DEC") (pin "5") (pinfunction "SDO_5") (pintype "unspecified"))
      (node (ref "DRV2/DEC") (pin "6") (pinfunction "CLK_6") (pintype "unspecified"))
      (node (ref "SWPI2") (pin "1") (pinfunction "1_1") (pintype "input"))
      (node (ref "TN1") (pin "5") (pinfunction "5_5") (pintype "input"))
    )
    (net (code "34") (name "DRV2_SR_PI") (class "Default")
      (node (ref "R23") (pin "2") (pinfunction "2_2") (pintype "input"))
      (node (ref "SWPI2") (pin "6") (pinfunction "6_6") (pintype "input"))
    )
    (net (code "35") (name "DRV2_STP") (class "Default")
      (node (ref "DRV2/DEC") (pin "7") (pinfunction "STEP_7") (pintype "unspecified"))
      (node (ref "SWPI2") (pin "2") (pinfunction "2_2") (pintype "input"))
      (node (ref "TN1") (pin "3") (pinfunction "3_3") (pintype "input"))
    )
    (net (code "36") (name "DRV2_STP_PI") (class "Default")
      (node (ref "R22") (pin "2") (pinfunction "2_2") (pintype "input"))
      (node (ref "SWPI2") (pin "5") (pinfunction "5_5") (pintype "input"))
    )
    (net (code "37") (name "DRV3_1A") (class "Default")
      (node (ref "DRV3/FOC") (pin "12") (pinfunction "B1_12") (pintype "unspecified"))
      (node (ref "RJ3") (pin "3") (pinfunction "3_3") (pintype "input"))
      (node (ref "RJ3") (pin "4") (pinfunction "4_4") (pintype "input"))
    )
    (net (code "38") (name "DRV3_1B") (class "Default")
      (node (ref "DRV3/FOC") (pin "11") (pinfunction "B2_11") (pintype "unspecified"))
      (node (ref "RJ3") (pin "1") (pinfunction "1_1") (pintype "input"))
      (node (ref "RJ3") (pin "2") (pinfunction "2_2") (pintype "input"))
    )
    (net (code "39") (name "DRV3_2A") (class "Default")
      (node (ref "DRV3/FOC") (pin "13") (pinfunction "A1_13") (pintype "unspecified"))
      (node (ref "RJ3") (pin "5") (pinfunction "5_5") (pintype "input"))
      (node (ref "RJ3") (pin "6") (pinfunction "6_6") (pintype "input"))
    )
    (net (code "40") (name "DRV3_2B") (class "Default")
      (node (ref "DRV3/FOC") (pin "14") (pinfunction "A2_14") (pintype "unspecified"))
      (node (ref "RJ3") (pin "7") (pinfunction "7_7") (pintype "input"))
      (node (ref "RJ3") (pin "8") (pinfunction "8_8") (pintype "input"))
    )
    (net (code "41") (name "DRV3_DIR") (class "Default")
      (node (ref "DRV3/FOC") (pin "8") (pinfunction "DIR_8") (pintype "unspecified"))
      (node (ref "U0") (pin "19") (pinfunction "(MOSI)_GPIO10_19") (pintype "unspecified"))
    )
    (net (code "42") (name "DRV3_M0") (class "Default")
      (node (ref "DRV3/FOC") (pin "2") (pinfunction "SDI_2") (pintype "unspecified"))
      (node (ref "SWM3") (pin "1") (pinfunction "1_1") (pintype "input"))
      (node (ref "SWPI3") (pin "3") (pinfunction "3_3") (pintype "input"))
    )
    (net (code "43") (name "DRV3_M1") (class "Default")
      (node (ref "DRV3/FOC") (pin "3") (pinfunction "SCK_3") (pintype "unspecified"))
      (node (ref "SWM3") (pin "2") (pinfunction "2_2") (pintype "input"))
      (node (ref "SWPI3") (pin "2") (pinfunction "2_2") (pintype "input"))
    )
    (net (code "44") (name "DRV3_M2") (class "Default")
      (node (ref "DRV3/FOC") (pin "4") (pinfunction "CSN_4") (pintype "unspecified"))
      (node (ref "SWM3") (pin "3") (pinfunction "3_3") (pintype "input"))
      (node (ref "SWPI3") (pin "1") (pinfunction "1_1") (pintype "input"))
    )
    (net (code "45") (name "DRV3_SR") (class "Default")
      (node (ref "DRV3/FOC") (pin "5") (pinfunction "SDO_5") (pintype "unspecified"))
      (node (ref "DRV3/FOC") (pin "6") (pinfunction "CLK_6") (pintype "unspecified"))
      (node (ref "U0") (pin "16") (pinfunction "GPIO23_16") (pintype "unspecified"))
    )
    (net (code "46") (name "DRV3_STP") (class "Default")
      (node (ref "DRV3/FOC") (pin "7") (pinfunction "STEP_7") (pintype "unspecified"))
      (node (ref "U0") (pin "18") (pinfunction "GPIO24_18") (pintype "unspecified"))
    )
    (net (code "47") (name "DRV4_1A") (class "Default")
      (node (ref "DRV4/ROT") (pin "12") (pinfunction "B1_12") (pintype "unspecified"))
      (node (ref "RJ4") (pin "3") (pinfunction "3_3") (pintype "input"))
      (node (ref "RJ4") (pin "4") (pinfunction "4_4") (pintype "input"))
    )
    (net (code "48") (name "DRV4_1B") (class "Default")
      (node (ref "DRV4/ROT") (pin "11") (pinfunction "B2_11") (pintype "unspecified"))
      (node (ref "RJ4") (pin "1") (pinfunction "1_1") (pintype "input"))
      (node (ref "RJ4") (pin "2") (pinfunction "2_2") (pintype "input"))
    )
    (net (code "49") (name "DRV4_2A") (class "Default")
      (node (ref "DRV4/ROT") (pin "13") (pinfunction "A1_13") (pintype "unspecified"))
      (node (ref "RJ4") (pin "5") (pinfunction "5_5") (pintype "input"))
      (node (ref "RJ4") (pin "6") (pinfunction "6_6") (pintype "input"))
    )
    (net (code "50") (name "DRV4_2B") (class "Default")
      (node (ref "DRV4/ROT") (pin "14") (pinfunction "A2_14") (pintype "unspecified"))
      (node (ref "RJ4") (pin "7") (pinfunction "7_7") (pintype "input"))
      (node (ref "RJ4") (pin "8") (pinfunction "8_8") (pintype "input"))
    )
    (net (code "51") (name "DRV4_DIR") (class "Default")
      (node (ref "DRV4/ROT") (pin "8") (pinfunction "DIR_8") (pintype "unspecified"))
      (node (ref "U0") (pin "13") (pinfunction "GPIO27_13") (pintype "unspecified"))
    )
    (net (code "52") (name "DRV4_M0") (class "Default")
      (node (ref "DRV4/ROT") (pin "2") (pinfunction "SDI_2") (pintype "unspecified"))
      (node (ref "SWM4") (pin "1") (pinfunction "1_1") (pintype "input"))
    )
    (net (code "53") (name "DRV4_M1") (class "Default")
      (node (ref "DRV4/ROT") (pin "3") (pinfunction "SCK_3") (pintype "unspecified"))
      (node (ref "SWM4") (pin "2") (pinfunction "2_2") (pintype "input"))
    )
    (net (code "54") (name "DRV4_M2") (class "Default")
      (node (ref "DRV4/ROT") (pin "4") (pinfunction "CSN_4") (pintype "unspecified"))
      (node (ref "SWM4") (pin "3") (pinfunction "3_3") (pintype "input"))
    )
    (net (code "55") (name "DRV4_SR") (class "Default")
      (node (ref "DRV4/ROT") (pin "5") (pinfunction "SDO_5") (pintype "unspecified"))
      (node (ref "DRV4/ROT") (pin "6") (pinfunction "CLK_6") (pintype "unspecified"))
      (node (ref "U0") (pin "11") (pinfunction "GPIO17_11") (pintype "unspecified"))
    )
    (net (code "56") (name "DRV4_STP") (class "Default")
      (node (ref "DRV4/ROT") (pin "7") (pinfunction "STEP_7") (pintype "unspecified"))
      (node (ref "U0") (pin "15") (pinfunction "GPIO22_15") (pintype "unspecified"))
    )
    (net (code "57") (name "DRV31_M0{slash}DIR_PI") (class "Default")
      (node (ref "R18") (pin "2") (pinfunction "2_2") (pintype "input"))
      (node (ref "SWPI1") (pin "4") (pinfunction "4_4") (pintype "input"))
      (node (ref "SWPI3") (pin "4") (pinfunction "4_4") (pintype "input"))
    )
    (net (code "58") (name "DRV31_M1{slash}STP_PI") (class "Default")
      (node (ref "R19") (pin "2") (pinfunction "2_2") (pintype "input"))
      (node (ref "SWPI1") (pin "5") (pinfunction "5_5") (pintype "input"))
      (node (ref "SWPI3") (pin "5") (pinfunction "5_5") (pintype "input"))
    )
    (net (code "59") (name "DRV31_M2{slash}SR_PI") (class "Default")
      (node (ref "R20") (pin "2") (pinfunction "2_2") (pintype "input"))
      (node (ref "SWPI1") (pin "6") (pinfunction "6_6") (pintype "input"))
      (node (ref "SWPI3") (pin "6") (pinfunction "6_6") (pintype "input"))
    )
    (net (code "60") (name "GND") (class "Default")
      (node (ref "C1") (pin "2") (pinfunction "2_2") (pintype "input"))
      (node (ref "C10") (pin "2") (pinfunction "2_2") (pintype "input"))
      (node (ref "C11") (pin "2") (pinfunction "2_2") (pintype "input"))
      (node (ref "C12") (pin "2") (pinfunction "2_2") (pintype "input"))
      (node (ref "C13") (pin "1") (pinfunction "1_1") (pintype "input"))
      (node (ref "C2") (pin "2") (pinfunction "2_2") (pintype "input"))
      (node (ref "C3") (pin "2") (pinfunction "2_2") (pintype "input"))
      (node (ref "C4") (pin "2") (pinfunction "2_2") (pintype "input"))
      (node (ref "C5") (pin "2") (pinfunction "2_2") (pintype "input"))
      (node (ref "C6") (pin "2") (pinfunction "2_2") (pintype "input"))
      (node (ref "C7") (pin "2") (pinfunction "2_2") (pintype "input"))
      (node (ref "C8") (pin "2") (pinfunction "2_2") (pintype "input"))
      (node (ref "C9") (pin "1") (pinfunction "1_1") (pintype "input"))
      (node (ref "CN1") (pin "1") (pinfunction "1_1") (pintype "input"))
      (node (ref "CN1") (pin "5") (pinfunction "5_5") (pintype "input"))
      (node (ref "CN2") (pin "1") (pinfunction "1_1") (pintype "input"))
      (node (ref "CN2") (pin "5") (pinfunction "5_5") (pintype "input"))
      (node (ref "DRV1/RA") (pin "15") (pinfunction "GND_15") (pintype "unspecified"))
      (node (ref "DRV1/RA") (pin "9") (pinfunction "GND_9") (pintype "unspecified"))
      (node (ref "DRV2/DEC") (pin "15") (pinfunction "GND_15") (pintype "unspecified"))
      (node (ref "DRV2/DEC") (pin "9") (pinfunction "GND_9") (pintype "unspecified"))
      (node (ref "DRV3/FOC") (pin "1") (pinfunction "EN_1") (pintype "unspecified"))
      (node (ref "DRV3/FOC") (pin "15") (pinfunction "GND_15") (pintype "unspecified"))
      (node (ref "DRV3/FOC") (pin "9") (pinfunction "GND_9") (pintype "unspecified"))
      (node (ref "DRV4/ROT") (pin "1") (pinfunction "EN_1") (pintype "unspecified"))
      (node (ref "DRV4/ROT") (pin "15") (pinfunction "GND_15") (pintype "unspecified"))
      (node (ref "DRV4/ROT") (pin "9") (pinfunction "GND_9") (pintype "unspecified"))
      (node (ref "GN0") (pin "1") (pinfunction "1_1") (pintype "unspecified"))
      (node (ref "GPS") (pin "4") (pinfunction "4_4") (pintype "input"))
      (node (ref "RJ1") (pin "10") (pinfunction "S_10") (pintype "input"))
      (node (ref "RJ1") (pin "9") (pinfunction "S_9") (pintype "input"))
      (node (ref "RJ2") (pin "10") (pinfunction "S_10") (pintype "input"))
      (node (ref "RJ2") (pin "9") (pinfunction "S_9") (pintype "input"))
      (node (ref "RJ3") (pin "10") (pinfunction "S_10") (pintype "input"))
      (node (ref "RJ3") (pin "9") (pinfunction "S_9") (pintype "input"))
      (node (ref "RJ4") (pin "10") (pinfunction "S_10") (pintype "input"))
      (node (ref "RJ4") (pin "9") (pinfunction "S_9") (pintype "input"))
      (node (ref "TN1") (pin "G1") (pinfunction "GND_G1") (pintype "input"))
      (node (ref "TN1") (pin "G2") (pinfunction "GND_G2") (pintype "input"))
      (node (ref "U0") (pin "14") (pinfunction "GND_14") (pintype "unspecified"))
      (node (ref "U0") (pin "20") (pinfunction "GND_20") (pintype "unspecified"))
      (node (ref "U0") (pin "25") (pinfunction "GND_25") (pintype "unspecified"))
      (node (ref "U0") (pin "30") (pinfunction "GND_30") (pintype "unspecified"))
      (node (ref "U0") (pin "34") (pinfunction "GND_34") (pintype "unspecified"))
      (node (ref "U0") (pin "39") (pinfunction "GND_39") (pintype "unspecified"))
      (node (ref "U0") (pin "41") (pinfunction "GND_41") (pintype "input"))
      (node (ref "U0") (pin "42") (pinfunction "GND_42") (pintype "input"))
      (node (ref "U0") (pin "43") (pinfunction "GND_43") (pintype "input"))
      (node (ref "U0") (pin "44") (pinfunction "GND_44") (pintype "input"))
      (node (ref "U0") (pin "45") (pinfunction "GND_45") (pintype "input"))
      (node (ref "U0") (pin "46") (pinfunction "GND_46") (pintype "input"))
      (node (ref "U0") (pin "6") (pinfunction "GND_6") (pintype "unspecified"))
      (node (ref "U0") (pin "9") (pinfunction "GND_9") (pintype "unspecified"))
      (node (ref "U17") (pin "4") (pinfunction "GND_4") (pintype "input"))
      (node (ref "U55") (pin "1") (pinfunction "1_1") (pintype "unspecified"))
      (node (ref "U55") (pin "3") (pinfunction "3_3") (pintype "unspecified"))
      (node (ref "U55") (pin "5") (pinfunction "5_5") (pintype "unspecified"))
      (node (ref "U75") (pin "5") (pinfunction "5_5") (pintype "unspecified"))
      (node (ref "U76") (pin "3") (pinfunction "GND_3") (pintype "unspecified"))
      (node (ref "U76") (pin "7") (pinfunction "A0_7") (pintype "unspecified"))
      (node (ref "U76") (pin "8") (pinfunction "A1_8") (pintype "unspecified"))
    )
    (net (code "61") (name "GPIO13_PWM1") (class "Default")
      (node (ref "U0") (pin "33") (pinfunction "(PWM1)_GPIO13_33") (pintype "unspecified"))
    )
    (net (code "62") (name "GPIO18_PWM0") (class "Default")
      (node (ref "U0") (pin "12") (pinfunction "(PWM0)_GPIO18_12") (pintype "unspecified"))
    )
    (net (code "63") (name "GPIO20") (class "Default")
      (node (ref "U0") (pin "38") (pinfunction "(MOSI)_GPIO20_38") (pintype "unspecified"))
    )
    (net (code "64") (name "GPIO21") (class "Default")
      (node (ref "U0") (pin "40") (pinfunction "(SCLK)_GPIO21_40") (pintype "unspecified"))
    )
    (net (code "65") (name "GPIO26") (class "Default")
      (node (ref "U0") (pin "37") (pinfunction "GPIO26_37") (pintype "unspecified"))
    )
    (net (code "66") (name "ID_SC") (class "Default")
      (node (ref "U0") (pin "28") (pinfunction "(ID_SC)_GPIO1_28") (pintype "unspecified"))
      (node (ref "U17") (pin "6") (pinfunction "SCL_6") (pintype "input"))
    )
    (net (code "67") (name "ID_SD") (class "Default")
      (node (ref "U0") (pin "27") (pinfunction "(ID_SD)_GPIO0_27") (pintype "unspecified"))
      (node (ref "U17") (pin "5") (pinfunction "SDA_5") (pintype "input"))
    )
    (net (code "68") (name "Net-(H4-Pad1)") (class "Default")
      (node (ref "H4") (pin "1") (pinfunction "1_1") (pintype "input"))
      (node (ref "U75") (pin "6") (pinfunction "6_6") (pintype "unspecified"))
    )
    (net (code "69") (name "Net-(LED1-+)") (class "Default")
      (node (ref "LED1") (pin "1") (pinfunction "+_1") (pintype "input"))
      (node (ref "R31") (pin "1") (pinfunction "1_1") (pintype "input"))
    )
    (net (code "70") (name "Net-(LED2-+)") (class "Default")
      (node (ref "LED2") (pin "1") (pinfunction "+_1") (pintype "input"))
      (node (ref "R32") (pin "1") (pinfunction "1_1") (pintype "input"))
    )
    (net (code "71") (name "Net-(R6-Pad1)") (class "Default")
      (node (ref "R6") (pin "1") (pinfunction "1_1") (pintype "input"))
      (node (ref "SWM1") (pin "6") (pinfunction "6_6") (pintype "input"))
    )
    (net (code "72") (name "Net-(R7-Pad1)") (class "Default")
      (node (ref "R7") (pin "1") (pinfunction "1_1") (pintype "input"))
      (node (ref "SWM1") (pin "5") (pinfunction "5_5") (pintype "input"))
    )
    (net (code "73") (name "Net-(R8-Pad1)") (class "Default")
      (node (ref "R8") (pin "1") (pinfunction "1_1") (pintype "input"))
      (node (ref "SWM1") (pin "4") (pinfunction "4_4") (pintype "input"))
    )
    (net (code "74") (name "Net-(R9-Pad1)") (class "Default")
      (node (ref "R9") (pin "1") (pinfunction "1_1") (pintype "input"))
      (node (ref "SWM2") (pin "6") (pinfunction "6_6") (pintype "input"))
    )
    (net (code "75") (name "Net-(R10-Pad1)") (class "Default")
      (node (ref "R10") (pin "1") (pinfunction "1_1") (pintype "input"))
      (node (ref "SWM2") (pin "5") (pinfunction "5_5") (pintype "input"))
    )
    (net (code "76") (name "Net-(R11-Pad1)") (class "Default")
      (node (ref "R11") (pin "1") (pinfunction "1_1") (pintype "input"))
      (node (ref "SWM2") (pin "4") (pinfunction "4_4") (pintype "input"))
    )
    (net (code "77") (name "Net-(R12-Pad1)") (class "Default")
      (node (ref "R12") (pin "1") (pinfunction "1_1") (pintype "input"))
      (node (ref "SWM3") (pin "6") (pinfunction "6_6") (pintype "input"))
    )
    (net (code "78") (name "Net-(R13-Pad1)") (class "Default")
      (node (ref "R13") (pin "1") (pinfunction "1_1") (pintype "input"))
      (node (ref "SWM3") (pin "5") (pinfunction "5_5") (pintype "input"))
    )
    (net (code "79") (name "Net-(R14-Pad1)") (class "Default")
      (node (ref "R14") (pin "1") (pinfunction "1_1") (pintype "input"))
      (node (ref "SWM3") (pin "4") (pinfunction "4_4") (pintype "input"))
    )
    (net (code "80") (name "Net-(R15-Pad1)") (class "Default")
      (node (ref "R15") (pin "1") (pinfunction "1_1") (pintype "input"))
      (node (ref "SWM4") (pin "6") (pinfunction "6_6") (pintype "input"))
    )
    (net (code "81") (name "Net-(R16-Pad1)") (class "Default")
      (node (ref "R16") (pin "1") (pinfunction "1_1") (pintype "input"))
      (node (ref "SWM4") (pin "5") (pinfunction "5_5") (pintype "input"))
    )
    (net (code "82") (name "Net-(R17-Pad1)") (class "Default")
      (node (ref "R17") (pin "1") (pinfunction "1_1") (pintype "input"))
      (node (ref "SWM4") (pin "4") (pinfunction "4_4") (pintype "input"))
    )
    (net (code "83") (name "Net-(R29-Pad2)") (class "Default")
      (node (ref "R29") (pin "2") (pinfunction "2_2") (pintype "input"))
      (node (ref "R30") (pin "2") (pinfunction "2_2") (pintype "input"))
    )
    (net (code "84") (name "Net-(U0-(CE1)_GPIO7)") (class "Default")
      (node (ref "R19") (pin "1") (pinfunction "1_1") (pintype "input"))
      (node (ref "U0") (pin "26") (pinfunction "(CE1)_GPIO7_26") (pintype "unspecified"))
    )
    (net (code "85") (name "Net-(U0-(MISO)_GPIO19)") (class "Default")
      (node (ref "R22") (pin "1") (pinfunction "1_1") (pintype "input"))
      (node (ref "U0") (pin "35") (pinfunction "(MISO)_GPIO19_35") (pintype "unspecified"))
    )
    (net (code "86") (name "Net-(U0-(SCLK)_GPIO11)") (class "Default")
      (node (ref "R18") (pin "1") (pinfunction "1_1") (pintype "input"))
      (node (ref "U0") (pin "23") (pinfunction "(SCLK)_GPIO11_23") (pintype "unspecified"))
    )
    (net (code "87") (name "Net-(U0-GPIO5)") (class "Default")
      (node (ref "R20") (pin "1") (pinfunction "1_1") (pintype "input"))
      (node (ref "U0") (pin "29") (pinfunction "GPIO5_29") (pintype "unspecified"))
    )
    (net (code "88") (name "Net-(U0-GPIO6)") (class "Default")
      (node (ref "R21") (pin "1") (pinfunction "1_1") (pintype "input"))
      (node (ref "U0") (pin "31") (pinfunction "GPIO6_31") (pintype "unspecified"))
    )
    (net (code "89") (name "Net-(U0-GPIO16)") (class "Default")
      (node (ref "R23") (pin "1") (pinfunction "1_1") (pintype "input"))
      (node (ref "U0") (pin "36") (pinfunction "GPIO16_36") (pintype "unspecified"))
    )
    (net (code "90") (name "Net-(U17-WP)") (class "Default")
      (node (ref "R5") (pin "1") (pinfunction "1_1") (pintype "input"))
      (node (ref "U17") (pin "7") (pinfunction "WP_7") (pintype "input"))
      (node (ref "WP0") (pin "1") (pinfunction "1_1") (pintype "unspecified"))
    )
    (net (code "91") (name "PEC") (class "Default")
      (node (ref "C12") (pin "1") (pinfunction "1_1") (pintype "input"))
      (node (ref "CN1") (pin "3") (pinfunction "3_3") (pintype "input"))
      (node (ref "CN1") (pin "7") (pinfunction "7_7") (pintype "input"))
      (node (ref "TN1") (pin "23") (pinfunction "CRX1_23") (pintype "input"))
    )
    (net (code "92") (name "PPS") (class "Default")
      (node (ref "GPS") (pin "1") (pinfunction "1_1") (pintype "input"))
      (node (ref "U0") (pin "22") (pinfunction "GPIO25_22") (pintype "unspecified"))
    )
    (net (code "93") (name "RA+") (class "Default")
      (node (ref "R27") (pin "2") (pinfunction "2_2") (pintype "input"))
      (node (ref "TN1") (pin "13") (pinfunction "SCK_13") (pintype "input"))
      (node (ref "U75") (pin "1") (pinfunction "1_1") (pintype "unspecified"))
    )
    (net (code "94") (name "RA-") (class "Default")
      (node (ref "R24") (pin "2") (pinfunction "2_2") (pintype "input"))
      (node (ref "TN1") (pin "10") (pinfunction "CS_10") (pintype "input"))
      (node (ref "U75") (pin "4") (pinfunction "4_4") (pintype "unspecified"))
    )
    (net (code "95") (name "RXD") (class "Default")
      (node (ref "GPS") (pin "3") (pinfunction "3_3") (pintype "input"))
      (node (ref "U0") (pin "10") (pinfunction "(RXD)_GPIO15_10") (pintype "unspecified"))
    )
    (net (code "96") (name "RX_ONSTEP") (class "Default")
      (node (ref "TN1") (pin "0") (pinfunction "CRX2,_RX1_0") (pintype "input"))
      (node (ref "U0") (pin "24") (pinfunction "(CE0)_GPIO8_24") (pintype "unspecified"))
    )
    (net (code "97") (name "SCL") (class "Default")
      (node (ref "U0") (pin "5") (pinfunction "(SCL)_GPIO3_5") (pintype "unspecified"))
      (node (ref "U76") (pin "5") (pinfunction "SCL_5") (pintype "unspecified"))
    )
    (net (code "98") (name "SDA") (class "Default")
      (node (ref "U0") (pin "3") (pinfunction "(SDA)_GPIO2_3") (pintype "unspecified"))
      (node (ref "U76") (pin "6") (pinfunction "SDA_6") (pintype "unspecified"))
    )
    (net (code "99") (name "TXD") (class "Default")
      (node (ref "GPS") (pin "2") (pinfunction "2_2") (pintype "input"))
      (node (ref "U0") (pin "8") (pinfunction "(TXD)_GPIO14_8") (pintype "unspecified"))
    )
    (net (code "100") (name "TX_ONSTEP") (class "Default")
      (node (ref "TN1") (pin "1") (pinfunction "CTX2,_TX1_1") (pintype "input"))
      (node (ref "U0") (pin "21") (pinfunction "(MISO)_GPIO9_21") (pintype "unspecified"))
    )
    (net (code "101") (name "unconnected-(CN1-Pad2)") (class "Default")
      (node (ref "CN1") (pin "2") (pinfunction "2_2") (pintype "input+no_connect"))
    )
    (net (code "102") (name "unconnected-(CN1-Pad6)") (class "Default")
      (node (ref "CN1") (pin "6") (pinfunction "6_6") (pintype "input+no_connect"))
    )
    (net (code "103") (name "unconnected-(CN2-Pad2)") (class "Default")
      (node (ref "CN2") (pin "2") (pinfunction "2_2") (pintype "input+no_connect"))
    )
    (net (code "104") (name "unconnected-(CN2-Pad6)") (class "Default")
      (node (ref "CN2") (pin "6") (pinfunction "6_6") (pintype "input+no_connect"))
    )
    (net (code "105") (name "unconnected-(TN1-3.3v-Pad26)") (class "Default")
      (node (ref "TN1") (pin "26") (pinfunction "3.3v_26") (pintype "input+no_connect"))
    )
    (net (code "106") (name "unconnected-(TN1-G3-Pad27)") (class "Default")
      (node (ref "TN1") (pin "27") (pinfunction "G3_27") (pintype "input+no_connect"))
    )
    (net (code "107") (name "unconnected-(TN1-OF-Pad29)") (class "Default")
      (node (ref "TN1") (pin "29") (pinfunction "OF_29") (pintype "input+no_connect"))
    )
    (net (code "108") (name "unconnected-(TN1-Program-Pad28)") (class "Default")
      (node (ref "TN1") (pin "28") (pinfunction "Program_28") (pintype "input+no_connect"))
    )
    (net (code "109") (name "unconnected-(TN1-VBat-Pad25)") (class "Default")
      (node (ref "TN1") (pin "25") (pinfunction "VBat_25") (pintype "input+no_connect"))
    )
    (net (code "110") (name "unconnected-(U0-(PWM0)_GPIO12-Pad32)") (class "Default")
      (node (ref "U0") (pin "32") (pinfunction "(PWM0)_GPIO12_32") (pintype "unspecified+no_connect"))
    )
    (net (code "111") (name "unconnected-(U17-A0-Pad1)") (class "Default")
      (node (ref "U17") (pin "1") (pinfunction "A0_1") (pintype "input+no_connect"))
    )
    (net (code "112") (name "unconnected-(U17-A1-Pad2)") (class "Default")
      (node (ref "U17") (pin "2") (pinfunction "A1_2") (pintype "input+no_connect"))
    )
  )
)
